# Relay_IO.net
KiCad netlist of a schematic drawn in Altium Designer
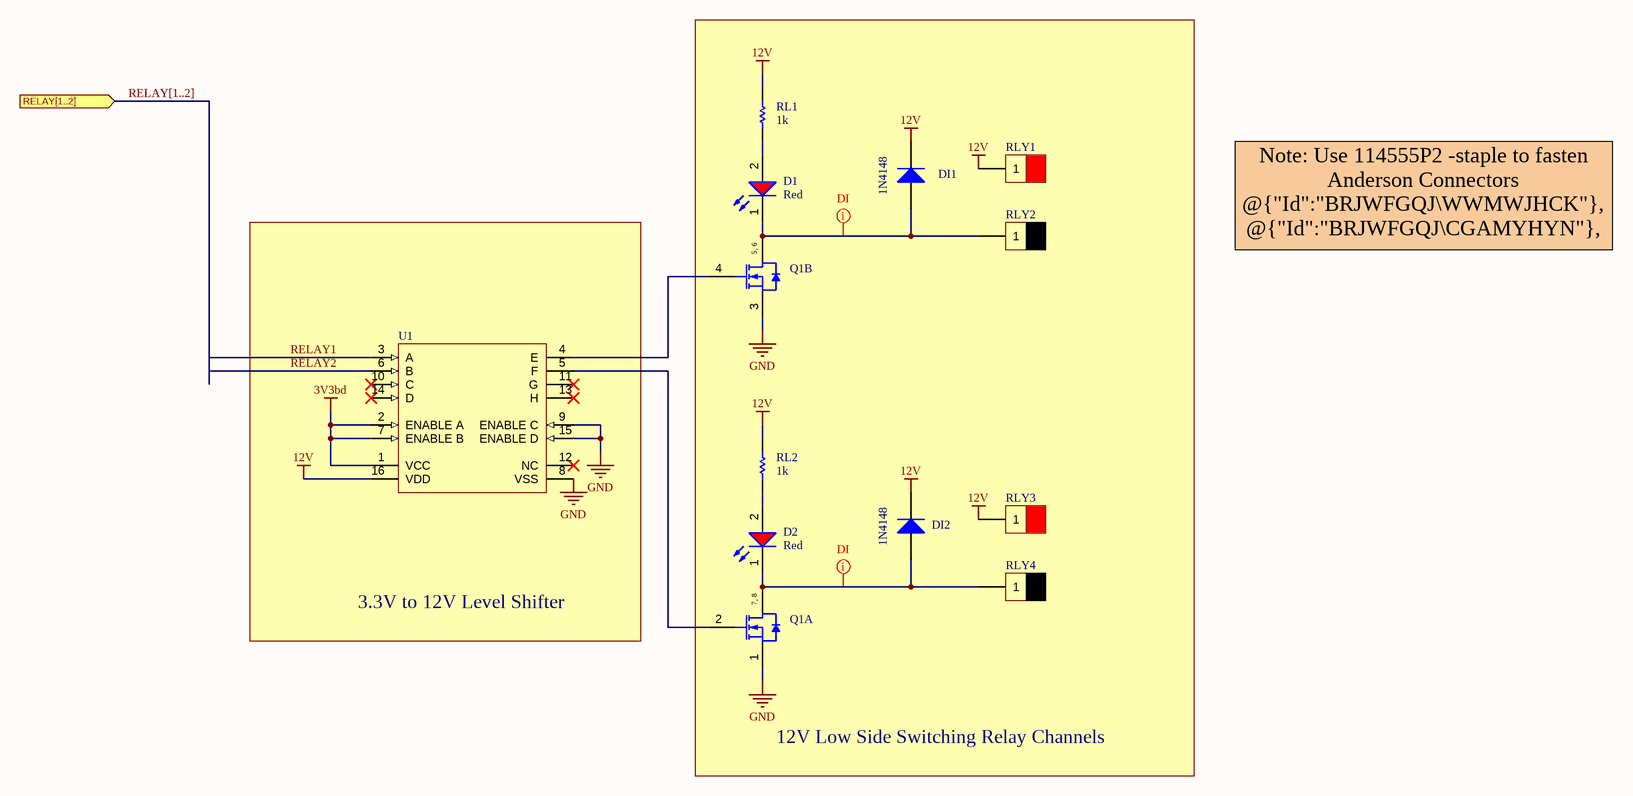
[diagram p0: Relay_IO.SchDoc]

(export (version "E")
  (design (tool "Eeschema 10.0.6"))
  (components
    (comp (ref "D1")
      (value "LED_Red0603")
      (footprint "0603_A")
      (description "Single Color LED, Red, Water Clear, 1.1mm")
      (fields (field (name "COLOR") "Red"))
      (libsource (lib "Advanced] Training Course - A365") (part "LED_Red_2A-1K"))
    )
    (comp (ref "D2")
      (value "LED_Red0603")
      (footprint "0603_A")
      (description "Single Color LED, Red, Water Clear, 1.1mm")
      (fields (field (name "COLOR") "Red"))
      (libsource (lib "Advanced] Training Course - A365") (part "LED_Red_2A-1K"))
    )
    (comp (ref "DI1")
      (value "1N4148")
      (footprint "DO-41")
      (description "Rectifier Diode, 1 Phase, 1 Element, 1A, 100V V(RRM), Silicon, DO-41")
      (libsource (lib "Advanced] Training Course - A365") (part "Diode  General"))
    )
    (comp (ref "DI2")
      (value "1N4148")
      (footprint "DO-41")
      (description "Rectifier Diode, 1 Phase, 1 Element, 1A, 100V V(RRM), Silicon, DO-41")
      (libsource (lib "Advanced] Training Course - A365") (part "Diode  General"))
    )
    (comp (ref "Q1")
      (value "NTHD4508NT1")
      (footprint "ONSC-CHIPFET-8-1206A-03_S2_V")
      (description "Small Signal Field-Effect Transistor")
      (libsource (lib "Advanced] Training Course - A365") (part "MOSFET Dual N-Channel"))
    )
    (comp (ref "RL1")
      (value "Res1K_0805")
      (footprint "0805_L")
      (fields
        (field (name "MANUFACTURER") "Panasonic Electronic Components")
        (field (name "MANUFACTURER PART NUMBER") "ERJ-6GEYJ102V")
        (field (name "RESISTANCE (OHMS)") "1k")
        (field (name "TOLERANCE") "5%")
      )
      (libsource (lib "Advanced] Training Course - A365") (part "Resistor General"))
    )
    (comp (ref "RL2")
      (value "Res1K_0805")
      (footprint "0805_L")
      (fields
        (field (name "MANUFACTURER") "Panasonic Electronic Components")
        (field (name "MANUFACTURER PART NUMBER") "ERJ-6GEYJ102V")
        (field (name "RESISTANCE (OHMS)") "1k")
        (field (name "TOLERANCE") "5%")
      )
      (libsource (lib "Advanced] Training Course - A365") (part "Resistor General"))
    )
    (comp (ref "RLY1")
      (value "Anderson-1Pin RED_PCB_RHT")
      (footprint "Anderson_RED_RHT_BOT")
      (description "Connector Accessory, Contact, Copper Alloy")
      (libsource (lib "TC - Altium Essentials Course A365 13") (part "Anderson-1Pin RED_PCB_RHT"))
    )
    (comp (ref "RLY2")
      (value "Anderson-1Pin BLK_PCB_RHT")
      (footprint "Anderson_BLK_RHT_BOT")
      (description "Connector Accessory, Contact, Copper Alloy")
      (libsource (lib "Advanced] Training Course - A365") (part "Anderson-1Pin BLK_PCB_RHT"))
    )
    (comp (ref "RLY3")
      (value "Anderson-1Pin RED_PCB_RHT")
      (footprint "Anderson_RED_RHT_BOT")
      (description "Connector Accessory, Contact, Copper Alloy")
      (libsource (lib "TC - Altium Essentials Course A365 13") (part "Anderson-1Pin RED_PCB_RHT"))
    )
    (comp (ref "RLY4")
      (value "Anderson-1Pin BLK_PCB_RHT")
      (footprint "Anderson_BLK_RHT_BOT")
      (description "Connector Accessory, Contact, Copper Alloy")
      (libsource (lib "Advanced] Training Course - A365") (part "Anderson-1Pin BLK_PCB_RHT"))
    )
    (comp (ref "U1")
      (value "CD40109BPW")
      (footprint "PW0016A_M")
      (fields
        (field (name "MANUFACTURER") "Texas Instruments")
        (field (name "MANUFACTURER PART NUMBER") "CD40109BPWR")
        (field (name "AVAILABLE PREVIEW IMAGES") "2D")
      )
      (libsource (lib "Advanced] Training Course - A365") (part "CD40109BPW"))
    )
  )
  (nets
    (net (code "1") (name "/RELAY1") (class "Default")
      (node (ref "U1") (pin "3") (pinfunction "A_3") (pintype "input"))
    )
    (net (code "2") (name "/RELAY2") (class "Default")
      (node (ref "U1") (pin "6") (pinfunction "B_6") (pintype "input"))
    )
    (net (code "4") (name "3V3bd") (class "Default")
      (node (ref "U1") (pin "1") (pinfunction "VCC_1") (pintype "power_in"))
      (node (ref "U1") (pin "2") (pinfunction "ENABLE_A_2") (pintype "input"))
      (node (ref "U1") (pin "7") (pinfunction "ENABLE_B_7") (pintype "input"))
    )
    (net (code "5") (name "12V") (class "Default")
      (node (ref "DI1") (pin "2") (pinfunction "K_2") (pintype "passive"))
      (node (ref "DI2") (pin "2") (pinfunction "K_2") (pintype "passive"))
      (node (ref "RL1") (pin "2") (pinfunction "2_2") (pintype "passive"))
      (node (ref "RL2") (pin "2") (pinfunction "2_2") (pintype "passive"))
      (node (ref "RLY1") (pin "1") (pinfunction "1_1") (pintype "passive"))
      (node (ref "RLY3") (pin "1") (pinfunction "1_1") (pintype "passive"))
      (node (ref "U1") (pin "16") (pinfunction "VDD_16") (pintype "power_in"))
    )
    (net (code "6") (name "GND") (class "Default")
      (node (ref "Q1") (pin "1") (pinfunction "S1_1") (pintype "passive"))
      (node (ref "Q1") (pin "3") (pinfunction "S2_3") (pintype "passive"))
      (node (ref "U1") (pin "15") (pinfunction "ENABLE_D_15") (pintype "input"))
      (node (ref "U1") (pin "8") (pinfunction "VSS_8") (pintype "power_in"))
      (node (ref "U1") (pin "9") (pinfunction "ENABLE_C_9") (pintype "input"))
    )
    (net (code "7") (name "Net-(D1-A)") (class "Default")
      (node (ref "D1") (pin "2") (pinfunction "A_2") (pintype "passive"))
      (node (ref "RL1") (pin "1") (pinfunction "1_1") (pintype "passive"))
    )
    (net (code "8") (name "Net-(D1-K)") (class "Default")
      (node (ref "D1") (pin "1") (pinfunction "K_1") (pintype "passive"))
      (node (ref "DI1") (pin "1") (pinfunction "A_1") (pintype "passive"))
      (node (ref "Q1") (pin "5") (pinfunction "D2_5") (pintype "passive"))
      (node (ref "Q1") (pin "6") (pinfunction "D2_6") (pintype "passive"))
      (node (ref "RLY2") (pin "1") (pinfunction "1_1") (pintype "passive"))
    )
    (net (code "9") (name "Net-(D2-A)") (class "Default")
      (node (ref "D2") (pin "2") (pinfunction "A_2") (pintype "passive"))
      (node (ref "RL2") (pin "1") (pinfunction "1_1") (pintype "passive"))
    )
    (net (code "10") (name "Net-(D2-K)") (class "Default")
      (node (ref "D2") (pin "1") (pinfunction "K_1") (pintype "passive"))
      (node (ref "DI2") (pin "1") (pinfunction "A_1") (pintype "passive"))
      (node (ref "Q1") (pin "7") (pinfunction "D1_7") (pintype "passive"))
      (node (ref "Q1") (pin "8") (pinfunction "D1_8") (pintype "passive"))
      (node (ref "RLY4") (pin "1") (pinfunction "1_1") (pintype "passive"))
    )
    (net (code "11") (name "Net-(Q1A-G1)") (class "Default")
      (node (ref "Q1") (pin "2") (pinfunction "G1_2") (pintype "passive"))
      (node (ref "U1") (pin "5") (pinfunction "F_5") (pintype "tri_state"))
    )
    (net (code "12") (name "Net-(Q1B-G2)") (class "Default")
      (node (ref "Q1") (pin "4") (pinfunction "G2_4") (pintype "passive"))
      (node (ref "U1") (pin "4") (pinfunction "E_4") (pintype "tri_state"))
    )
    (net (code "13") (name "unconnected-(U1-C-Pad10)") (class "Default")
      (node (ref "U1") (pin "10") (pinfunction "C_10") (pintype "input+no_connect"))
    )
    (net (code "14") (name "unconnected-(U1-D-Pad14)") (class "Default")
      (node (ref "U1") (pin "14") (pinfunction "D_14") (pintype "input+no_connect"))
    )
    (net (code "15") (name "unconnected-(U1-G-Pad11)") (class "Default")
      (node (ref "U1") (pin "11") (pinfunction "G_11") (pintype "tri_state+no_connect"))
    )
    (net (code "16") (name "unconnected-(U1-H-Pad13)") (class "Default")
      (node (ref "U1") (pin "13") (pinfunction "H_13") (pintype "tri_state+no_connect"))
    )
    (net (code "17") (name "unconnected-(U1-NC-Pad12)") (class "Default")
      (node (ref "U1") (pin "12") (pinfunction "NC_12") (pintype "passive+no_connect"))
    )
  )
)
